# untitled.net
KiCad netlist of a schematic drawn in EAGLE
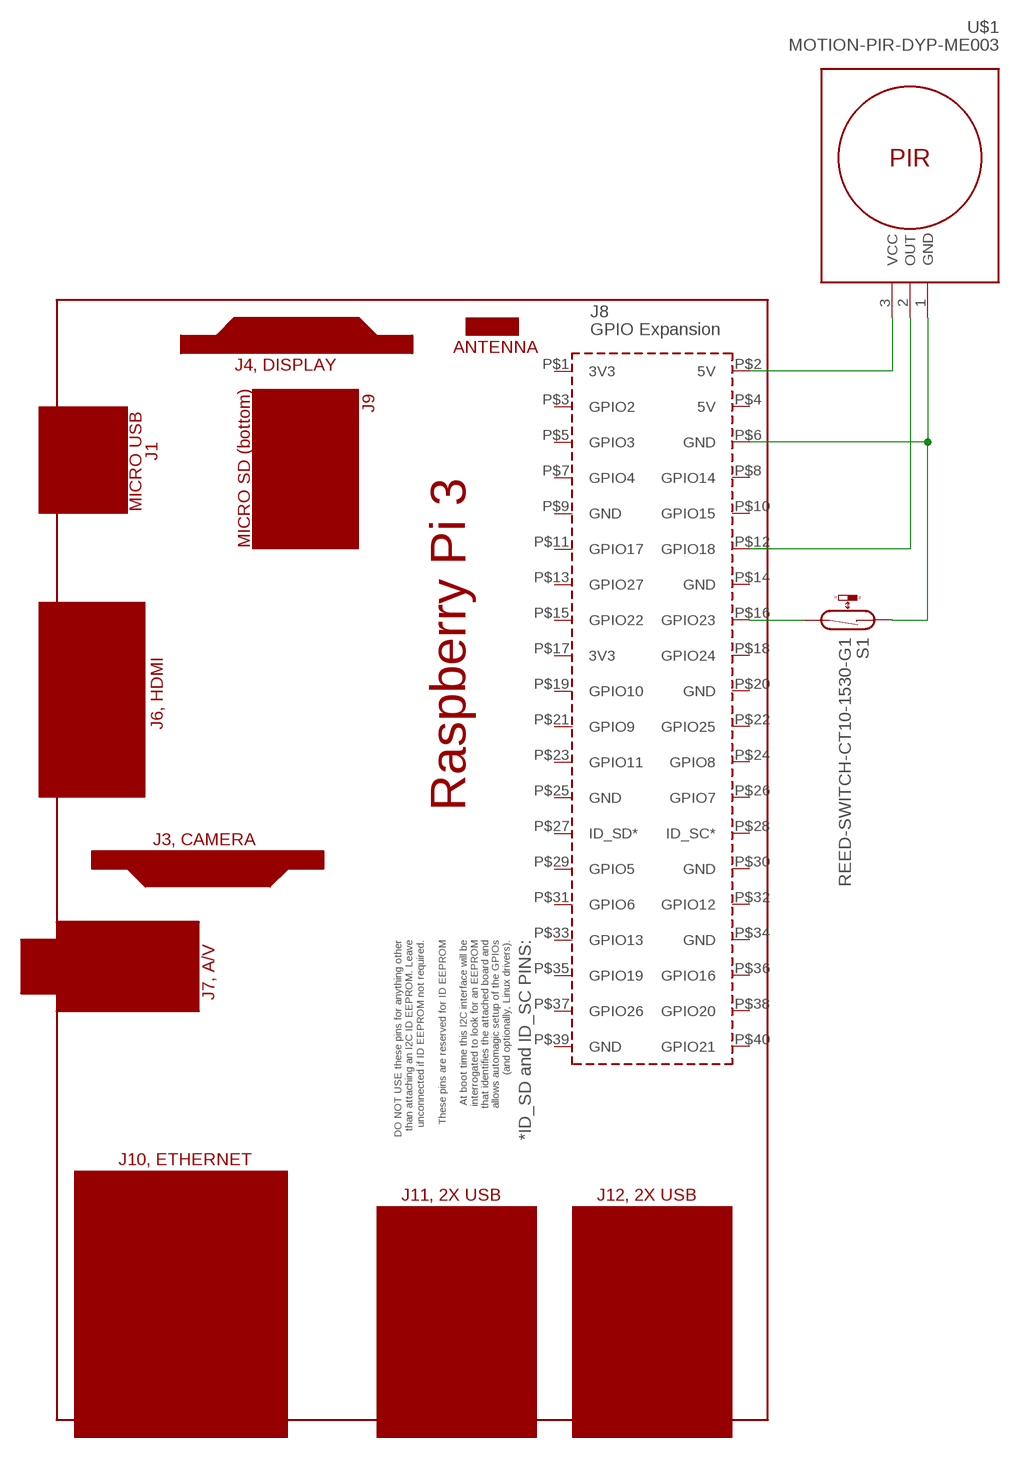
[diagram p0: schematic, sheet 1]

(export (version "E")
  (design (tool "Eeschema 10.0.6"))
  (components
    (comp (ref "PCB1")
      (value "RPI3RPI3")
      (footprint "eagle-import:RPI3")
      (libsource (lib "eagle-import") (part "RPI3RPI3"))
    )
    (comp (ref "S1")
      (value "REED-SWITCH-CT10-1530-G1")
      (footprint "eagle-import:CT10-G1")
      (fields (field (name "MF") "COTO TECHNOLOGY") (field (name "MPN") "CT10-1530-G1"))
      (libsource (lib "eagle-import") (part "REED-SWITCH-CT10-1530-G1"))
    )
    (comp (ref "U$1")
      (value "MOTION-PIR-DYP-ME003")
      (footprint "eagle-import:MOTION-PIR-DYP-ME003")
      (libsource (lib "eagle-import") (part "MOTION-PIR-DYP-ME003"))
    )
  )
  (nets
    (net (code "1") (name "Net-(PCB1-GPIO18)") (class "Default")
      (node (ref "PCB1") (pin "P$12") (pinfunction "GPIO18_P$12") (pintype "bidirectional"))
      (node (ref "U$1") (pin "2") (pinfunction "OUT_2") (pintype "output"))
    )
    (net (code "2") (name "Net-(PCB1-GPIO23)") (class "Default")
      (node (ref "PCB1") (pin "P$16") (pinfunction "GPIO23_P$16") (pintype "bidirectional"))
      (node (ref "S1") (pin "2") (pinfunction "2_2") (pintype "passive"))
    )
    (net (code "3") (name "Net-(U$1-GND)") (class "Default")
      (node (ref "PCB1") (pin "P$6") (pinfunction "GND_P$6") (pintype "bidirectional"))
      (node (ref "S1") (pin "1") (pinfunction "1_1") (pintype "passive"))
      (node (ref "U$1") (pin "1") (pinfunction "GND_1") (pintype "power_in"))
    )
    (net (code "4") (name "Net-(U$1-VCC)") (class "Default")
      (node (ref "PCB1") (pin "P$2") (pinfunction "5V_P$2") (pintype "bidirectional"))
      (node (ref "U$1") (pin "3") (pinfunction "VCC_3") (pintype "power_in"))
    )
    (net (code "5") (name "unconnected-(PCB1-3V3-PadP$1)") (class "Default")
      (node (ref "PCB1") (pin "P$1") (pinfunction "3V3_P$1") (pintype "bidirectional"))
    )
    (net (code "6") (name "unconnected-(PCB1-3V3-PadP$17)") (class "Default")
      (node (ref "PCB1") (pin "P$17") (pinfunction "3V3_P$17") (pintype "bidirectional"))
    )
    (net (code "7") (name "unconnected-(PCB1-5V-PadP$4)") (class "Default")
      (node (ref "PCB1") (pin "P$4") (pinfunction "5V_P$4") (pintype "bidirectional"))
    )
    (net (code "8") (name "unconnected-(PCB1-GND-PadP$9)") (class "Default")
      (node (ref "PCB1") (pin "P$9") (pinfunction "GND_P$9") (pintype "bidirectional"))
    )
    (net (code "9") (name "unconnected-(PCB1-GND-PadP$14)") (class "Default")
      (node (ref "PCB1") (pin "P$14") (pinfunction "GND_P$14") (pintype "bidirectional"))
    )
    (net (code "10") (name "unconnected-(PCB1-GND-PadP$20)") (class "Default")
      (node (ref "PCB1") (pin "P$20") (pinfunction "GND_P$20") (pintype "bidirectional"))
    )
    (net (code "11") (name "unconnected-(PCB1-GND-PadP$25)") (class "Default")
      (node (ref "PCB1") (pin "P$25") (pinfunction "GND_P$25") (pintype "bidirectional"))
    )
    (net (code "12") (name "unconnected-(PCB1-GND-PadP$30)") (class "Default")
      (node (ref "PCB1") (pin "P$30") (pinfunction "GND_P$30") (pintype "bidirectional"))
    )
    (net (code "13") (name "unconnected-(PCB1-GND-PadP$34)") (class "Default")
      (node (ref "PCB1") (pin "P$34") (pinfunction "GND_P$34") (pintype "bidirectional"))
    )
    (net (code "14") (name "unconnected-(PCB1-GND-PadP$39)") (class "Default")
      (node (ref "PCB1") (pin "P$39") (pinfunction "GND_P$39") (pintype "bidirectional"))
    )
    (net (code "15") (name "unconnected-(PCB1-GPIO2-PadP$3)") (class "Default")
      (node (ref "PCB1") (pin "P$3") (pinfunction "GPIO2_P$3") (pintype "bidirectional"))
    )
    (net (code "16") (name "unconnected-(PCB1-GPIO3-PadP$5)") (class "Default")
      (node (ref "PCB1") (pin "P$5") (pinfunction "GPIO3_P$5") (pintype "bidirectional"))
    )
    (net (code "17") (name "unconnected-(PCB1-GPIO4-PadP$7)") (class "Default")
      (node (ref "PCB1") (pin "P$7") (pinfunction "GPIO4_P$7") (pintype "bidirectional"))
    )
    (net (code "18") (name "unconnected-(PCB1-GPIO5-PadP$29)") (class "Default")
      (node (ref "PCB1") (pin "P$29") (pinfunction "GPIO5_P$29") (pintype "bidirectional"))
    )
    (net (code "19") (name "unconnected-(PCB1-GPIO6-PadP$31)") (class "Default")
      (node (ref "PCB1") (pin "P$31") (pinfunction "GPIO6_P$31") (pintype "bidirectional"))
    )
    (net (code "20") (name "unconnected-(PCB1-GPIO7-PadP$26)") (class "Default")
      (node (ref "PCB1") (pin "P$26") (pinfunction "GPIO7_P$26") (pintype "bidirectional"))
    )
    (net (code "21") (name "unconnected-(PCB1-GPIO8-PadP$24)") (class "Default")
      (node (ref "PCB1") (pin "P$24") (pinfunction "GPIO8_P$24") (pintype "bidirectional"))
    )
    (net (code "22") (name "unconnected-(PCB1-GPIO9-PadP$21)") (class "Default")
      (node (ref "PCB1") (pin "P$21") (pinfunction "GPIO9_P$21") (pintype "bidirectional"))
    )
    (net (code "23") (name "unconnected-(PCB1-GPIO10-PadP$19)") (class "Default")
      (node (ref "PCB1") (pin "P$19") (pinfunction "GPIO10_P$19") (pintype "bidirectional"))
    )
    (net (code "24") (name "unconnected-(PCB1-GPIO11-PadP$23)") (class "Default")
      (node (ref "PCB1") (pin "P$23") (pinfunction "GPIO11_P$23") (pintype "bidirectional"))
    )
    (net (code "25") (name "unconnected-(PCB1-GPIO12-PadP$32)") (class "Default")
      (node (ref "PCB1") (pin "P$32") (pinfunction "GPIO12_P$32") (pintype "bidirectional"))
    )
    (net (code "26") (name "unconnected-(PCB1-GPIO13-PadP$33)") (class "Default")
      (node (ref "PCB1") (pin "P$33") (pinfunction "GPIO13_P$33") (pintype "bidirectional"))
    )
    (net (code "27") (name "unconnected-(PCB1-GPIO14-PadP$8)") (class "Default")
      (node (ref "PCB1") (pin "P$8") (pinfunction "GPIO14_P$8") (pintype "bidirectional"))
    )
    (net (code "28") (name "unconnected-(PCB1-GPIO15-PadP$10)") (class "Default")
      (node (ref "PCB1") (pin "P$10") (pinfunction "GPIO15_P$10") (pintype "bidirectional"))
    )
    (net (code "29") (name "unconnected-(PCB1-GPIO16-PadP$36)") (class "Default")
      (node (ref "PCB1") (pin "P$36") (pinfunction "GPIO16_P$36") (pintype "bidirectional"))
    )
    (net (code "30") (name "unconnected-(PCB1-GPIO17-PadP$11)") (class "Default")
      (node (ref "PCB1") (pin "P$11") (pinfunction "GPIO17_P$11") (pintype "bidirectional"))
    )
    (net (code "31") (name "unconnected-(PCB1-GPIO19-PadP$35)") (class "Default")
      (node (ref "PCB1") (pin "P$35") (pinfunction "GPIO19_P$35") (pintype "bidirectional"))
    )
    (net (code "32") (name "unconnected-(PCB1-GPIO20-PadP$38)") (class "Default")
      (node (ref "PCB1") (pin "P$38") (pinfunction "GPIO20_P$38") (pintype "bidirectional"))
    )
    (net (code "33") (name "unconnected-(PCB1-GPIO21-PadP$40)") (class "Default")
      (node (ref "PCB1") (pin "P$40") (pinfunction "GPIO21_P$40") (pintype "bidirectional"))
    )
    (net (code "34") (name "unconnected-(PCB1-GPIO22-PadP$15)") (class "Default")
      (node (ref "PCB1") (pin "P$15") (pinfunction "GPIO22_P$15") (pintype "bidirectional"))
    )
    (net (code "35") (name "unconnected-(PCB1-GPIO24-PadP$18)") (class "Default")
      (node (ref "PCB1") (pin "P$18") (pinfunction "GPIO24_P$18") (pintype "bidirectional"))
    )
    (net (code "36") (name "unconnected-(PCB1-GPIO25-PadP$22)") (class "Default")
      (node (ref "PCB1") (pin "P$22") (pinfunction "GPIO25_P$22") (pintype "bidirectional"))
    )
    (net (code "37") (name "unconnected-(PCB1-GPIO26-PadP$37)") (class "Default")
      (node (ref "PCB1") (pin "P$37") (pinfunction "GPIO26_P$37") (pintype "bidirectional"))
    )
    (net (code "38") (name "unconnected-(PCB1-GPIO27-PadP$13)") (class "Default")
      (node (ref "PCB1") (pin "P$13") (pinfunction "GPIO27_P$13") (pintype "bidirectional"))
    )
    (net (code "39") (name "unconnected-(PCB1-ID_SC*-PadP$28)") (class "Default")
      (node (ref "PCB1") (pin "P$28") (pinfunction "ID_SC*_P$28") (pintype "bidirectional"))
    )
    (net (code "40") (name "unconnected-(PCB1-ID_SD*-PadP$27)") (class "Default")
      (node (ref "PCB1") (pin "P$27") (pinfunction "ID_SD*_P$27") (pintype "bidirectional"))
    )
  )
)
